# Connectors.net
KiCad netlist of a schematic drawn in Altium Designer
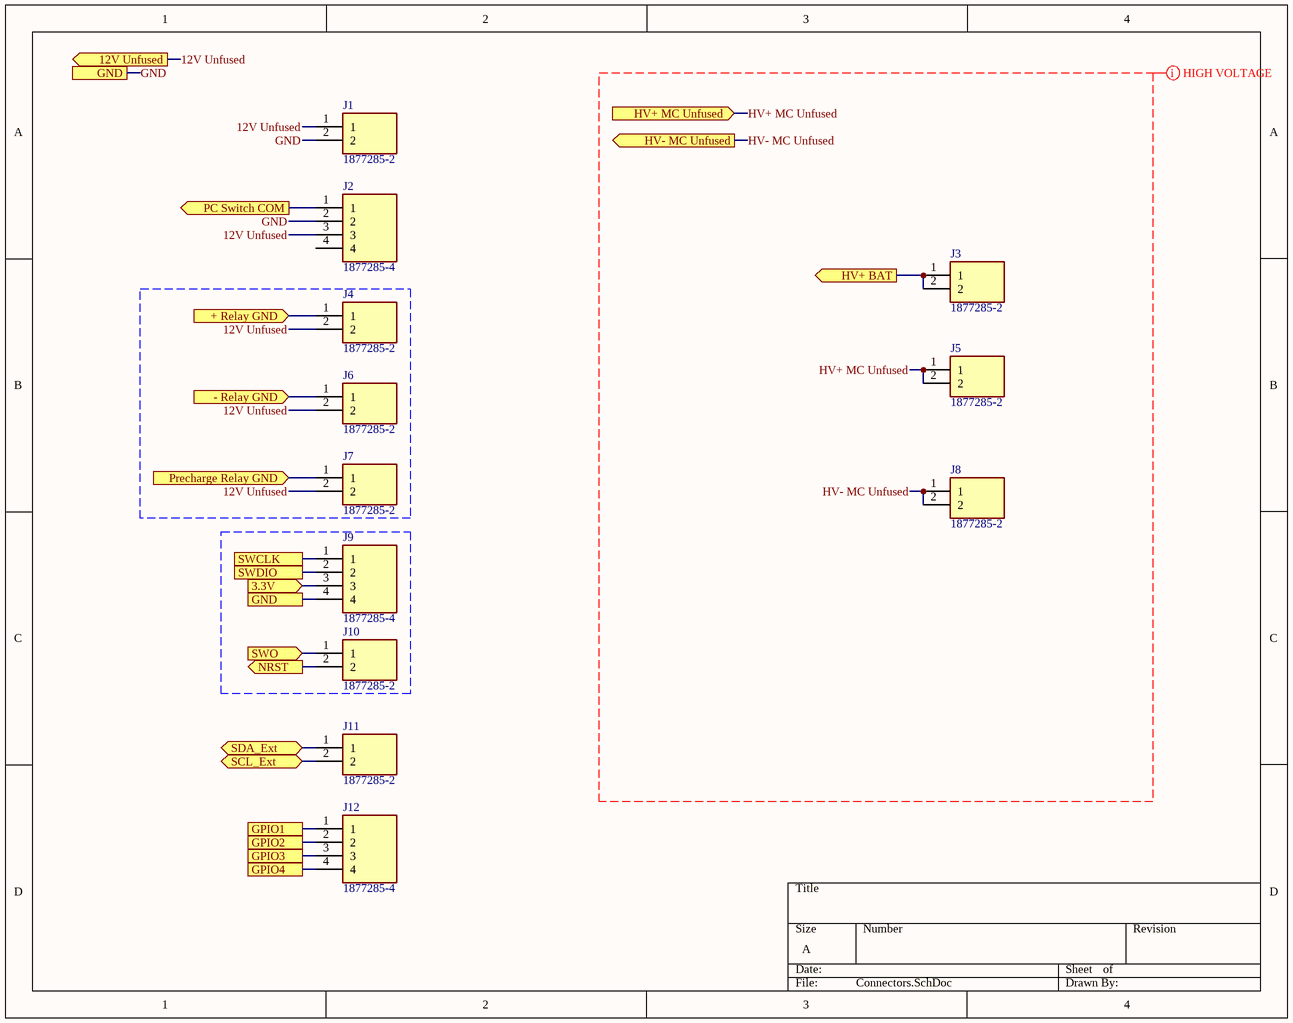
[diagram p0: Connectors.SchDoc]

(export (version "E")
  (design (tool "Eeschema 10.0.6"))
  (components
    (comp (ref "J1")
      (value "1877285-2")
      (footprint "SamacSys:18772852")
      (description "Connector")
      (fields (field (name "MOUSER PART NUMBER") "571-1877285-2"))
      (libsource (lib "SamacSys") (part "1877285-2"))
    )
    (comp (ref "J2")
      (value "1877285-4")
      (footprint "SamacSys:18772854")
      (description "Connector")
      (fields (field (name "MOUSER PART NUMBER") "571-1877285-4"))
      (libsource (lib "SamacSys") (part "1877285-4"))
    )
    (comp (ref "J3")
      (value "1877285-2")
      (footprint "SamacSys:18772852")
      (description "Connector")
      (fields (field (name "MOUSER PART NUMBER") "571-1877285-2"))
      (libsource (lib "SamacSys") (part "1877285-2"))
    )
    (comp (ref "J4")
      (value "1877285-2")
      (footprint "SamacSys:18772852")
      (description "Connector")
      (fields (field (name "MOUSER PART NUMBER") "571-1877285-2"))
      (libsource (lib "SamacSys") (part "1877285-2"))
    )
    (comp (ref "J5")
      (value "1877285-2")
      (footprint "SamacSys:18772852")
      (description "Connector")
      (fields (field (name "MOUSER PART NUMBER") "571-1877285-2"))
      (libsource (lib "SamacSys") (part "1877285-2"))
    )
    (comp (ref "J6")
      (value "1877285-2")
      (footprint "SamacSys:18772852")
      (description "Connector")
      (fields (field (name "MOUSER PART NUMBER") "571-1877285-2"))
      (libsource (lib "SamacSys") (part "1877285-2"))
    )
    (comp (ref "J7")
      (value "1877285-2")
      (footprint "SamacSys:18772852")
      (description "Connector")
      (fields (field (name "MOUSER PART NUMBER") "571-1877285-2"))
      (libsource (lib "SamacSys") (part "1877285-2"))
    )
    (comp (ref "J8")
      (value "1877285-2")
      (footprint "SamacSys:18772852")
      (description "Connector")
      (fields (field (name "MOUSER PART NUMBER") "571-1877285-2"))
      (libsource (lib "SamacSys") (part "1877285-2"))
    )
    (comp (ref "J9")
      (value "1877285-4")
      (footprint "SamacSys:18772854")
      (description "Connector")
      (fields (field (name "MOUSER PART NUMBER") "571-1877285-4"))
      (libsource (lib "SamacSys") (part "1877285-4"))
    )
    (comp (ref "J10")
      (value "1877285-2")
      (footprint "SamacSys:18772852")
      (description "Connector")
      (fields (field (name "MOUSER PART NUMBER") "571-1877285-2"))
      (libsource (lib "SamacSys") (part "1877285-2"))
    )
    (comp (ref "J11")
      (value "1877285-2")
      (footprint "SamacSys:18772852")
      (description "Connector")
      (fields (field (name "MOUSER PART NUMBER") "571-1877285-2"))
      (libsource (lib "SamacSys") (part "1877285-2"))
    )
    (comp (ref "J12")
      (value "1877285-4")
      (footprint "SamacSys:18772854")
      (description "Connector")
      (fields (field (name "MOUSER PART NUMBER") "571-1877285-4"))
      (libsource (lib "SamacSys") (part "1877285-4"))
    )
  )
  (nets
    (net (code "1") (name "/+ Relay GND") (class "Default")
      (node (ref "J4") (pin "1") (pinfunction "1_1") (pintype "passive"))
    )
    (net (code "2") (name "/- Relay GND") (class "Default")
      (node (ref "J6") (pin "1") (pinfunction "1_1") (pintype "passive"))
    )
    (net (code "3") (name "/3.3V") (class "Default")
      (node (ref "J9") (pin "3") (pinfunction "3_3") (pintype "passive"))
    )
    (net (code "4") (name "/12V Unfused") (class "Default")
      (node (ref "J1") (pin "1") (pinfunction "1_1") (pintype "passive"))
      (node (ref "J2") (pin "3") (pinfunction "3_3") (pintype "passive"))
      (node (ref "J4") (pin "2") (pinfunction "2_2") (pintype "passive"))
      (node (ref "J6") (pin "2") (pinfunction "2_2") (pintype "passive"))
      (node (ref "J7") (pin "2") (pinfunction "2_2") (pintype "passive"))
    )
    (net (code "5") (name "/GND") (class "Default")
      (node (ref "J1") (pin "2") (pinfunction "2_2") (pintype "passive"))
      (node (ref "J2") (pin "2") (pinfunction "2_2") (pintype "passive"))
      (node (ref "J9") (pin "4") (pinfunction "4_4") (pintype "passive"))
    )
    (net (code "6") (name "/GPIO1") (class "Default")
      (node (ref "J12") (pin "1") (pinfunction "1_1") (pintype "passive"))
    )
    (net (code "7") (name "/GPIO2") (class "Default")
      (node (ref "J12") (pin "2") (pinfunction "2_2") (pintype "passive"))
    )
    (net (code "8") (name "/GPIO3") (class "Default")
      (node (ref "J12") (pin "3") (pinfunction "3_3") (pintype "passive"))
    )
    (net (code "9") (name "/GPIO4") (class "Default")
      (node (ref "J12") (pin "4") (pinfunction "4_4") (pintype "passive"))
    )
    (net (code "10") (name "/HV+ BAT") (class "Default")
      (node (ref "J3") (pin "1") (pinfunction "1_1") (pintype "passive"))
      (node (ref "J3") (pin "2") (pinfunction "2_2") (pintype "passive"))
    )
    (net (code "11") (name "/HV+ MC Unfused") (class "Default")
      (node (ref "J5") (pin "1") (pinfunction "1_1") (pintype "passive"))
      (node (ref "J5") (pin "2") (pinfunction "2_2") (pintype "passive"))
    )
    (net (code "12") (name "/HV- MC Unfused") (class "Default")
      (node (ref "J8") (pin "1") (pinfunction "1_1") (pintype "passive"))
      (node (ref "J8") (pin "2") (pinfunction "2_2") (pintype "passive"))
    )
    (net (code "13") (name "/NRST") (class "Default")
      (node (ref "J10") (pin "2") (pinfunction "2_2") (pintype "passive"))
    )
    (net (code "14") (name "/PC Switch COM") (class "Default")
      (node (ref "J2") (pin "1") (pinfunction "1_1") (pintype "passive"))
    )
    (net (code "15") (name "/Precharge Relay GND") (class "Default")
      (node (ref "J7") (pin "1") (pinfunction "1_1") (pintype "passive"))
    )
    (net (code "16") (name "/SCL_Ext") (class "Default")
      (node (ref "J11") (pin "2") (pinfunction "2_2") (pintype "passive"))
    )
    (net (code "17") (name "/SDA_Ext") (class "Default")
      (node (ref "J11") (pin "1") (pinfunction "1_1") (pintype "passive"))
    )
    (net (code "18") (name "/SWCLK") (class "Default")
      (node (ref "J9") (pin "1") (pinfunction "1_1") (pintype "passive"))
    )
    (net (code "19") (name "/SWDIO") (class "Default")
      (node (ref "J9") (pin "2") (pinfunction "2_2") (pintype "passive"))
    )
    (net (code "20") (name "/SWO") (class "Default")
      (node (ref "J10") (pin "1") (pinfunction "1_1") (pintype "passive"))
    )
    (net (code "21") (name "unconnected-(J2-Pad4)") (class "Default")
      (node (ref "J2") (pin "4") (pinfunction "4_4") (pintype "passive"))
    )
  )
)
